# schema.net
KiCad netlist of a schematic drawn in Altium Designer
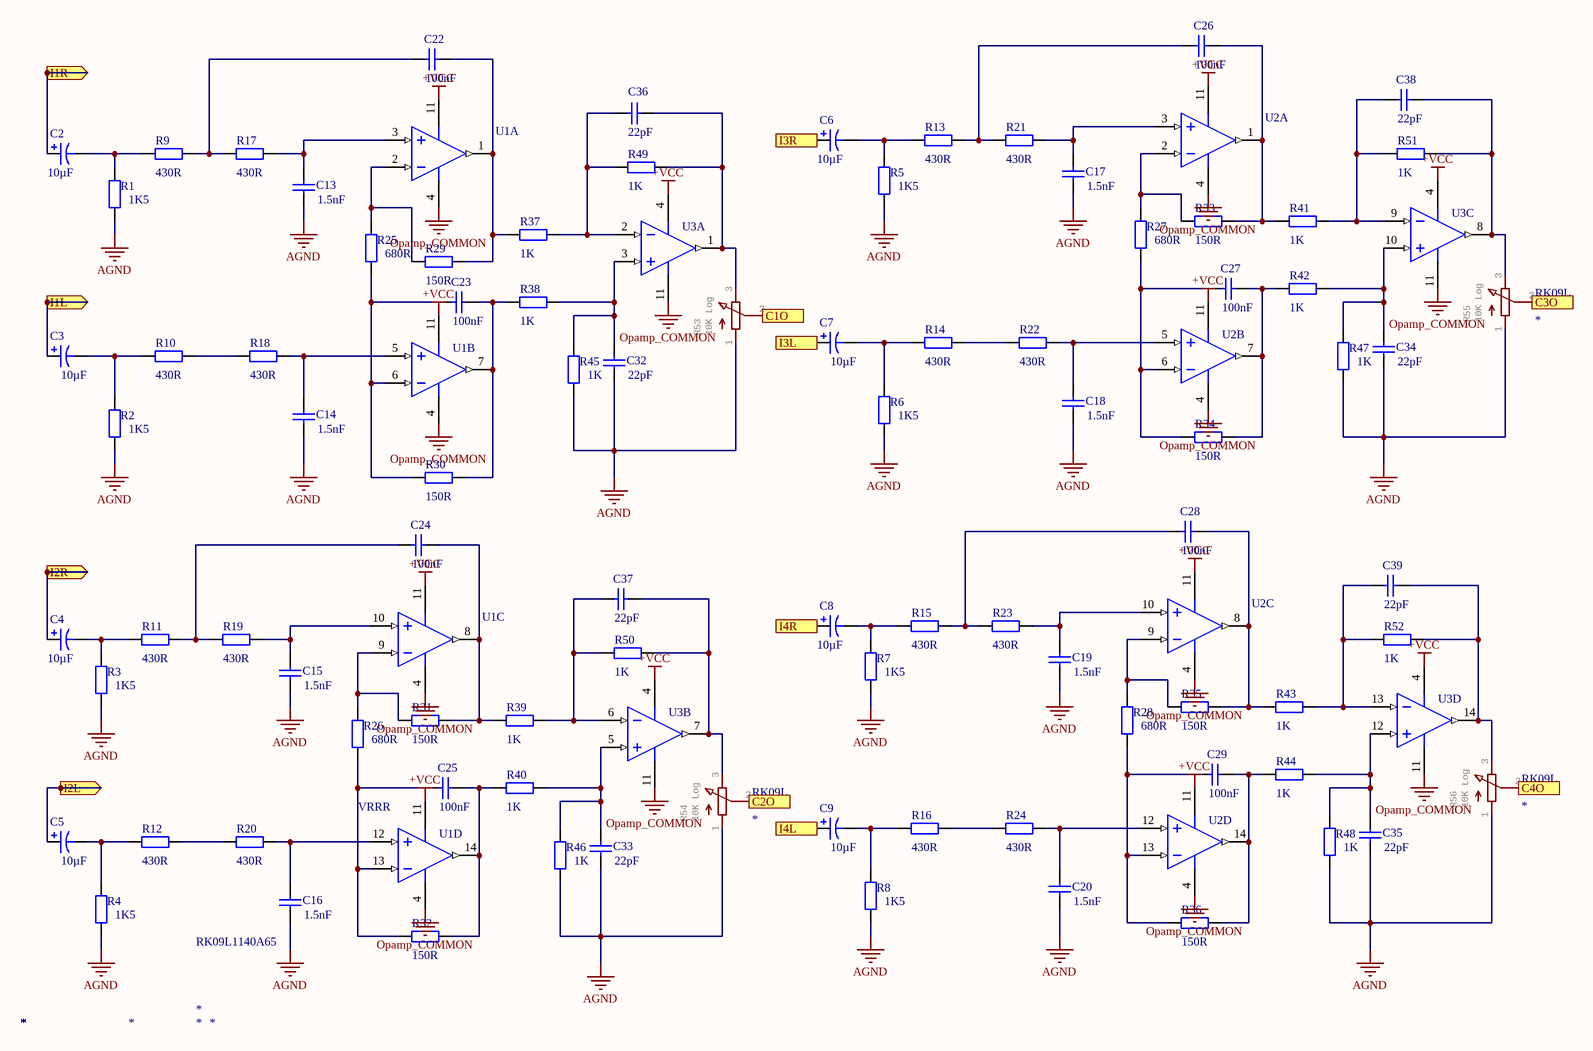
[diagram p0: schema.SchDoc]

(export (version "E")
  (design (tool "Eeschema 10.0.6"))
  (components
    (comp (ref "C2")
      (value "10µF")
      (footprint "SMD_POLAR_CAPACITOR")
      (description "Polarized Capacitor (Radial)")
      (fields (field (name "Comment") "Cap Pol1") (field (name "PUBLISHER") "Altium Limited"))
      (libsource (lib "equalizer_project") (part "Cap Pol1"))
    )
    (comp (ref "C3")
      (value "10µF")
      (footprint "SMD_POLAR_CAPACITOR")
      (description "Polarized Capacitor (Radial)")
      (fields (field (name "Comment") "Cap Pol1") (field (name "PUBLISHER") "Altium Limited"))
      (libsource (lib "Miscellaneous Devices") (part "Cap Pol1"))
    )
    (comp (ref "C4")
      (value "10µF")
      (footprint "SMD_POLAR_CAPACITOR")
      (description "Polarized Capacitor (Radial)")
      (fields (field (name "Comment") "Cap Pol1") (field (name "PUBLISHER") "Altium Limited"))
      (libsource (lib "Miscellaneous Devices") (part "Cap Pol1"))
    )
    (comp (ref "C5")
      (value "10µF")
      (footprint "SMD_POLAR_CAPACITOR")
      (description "Polarized Capacitor (Radial)")
      (fields (field (name "Comment") "Cap Pol1") (field (name "PUBLISHER") "Altium Limited"))
      (libsource (lib "Miscellaneous Devices") (part "Cap Pol1"))
    )
    (comp (ref "C6")
      (value "10µF")
      (footprint "SMD_POLAR_CAPACITOR")
      (description "Polarized Capacitor (Radial)")
      (fields (field (name "Comment") "Cap Pol1") (field (name "PUBLISHER") "Altium Limited"))
      (libsource (lib "Miscellaneous Devices") (part "Cap Pol1"))
    )
    (comp (ref "C7")
      (value "10µF")
      (footprint "SMD_POLAR_CAPACITOR")
      (description "Polarized Capacitor (Radial)")
      (fields (field (name "Comment") "Cap Pol1") (field (name "PUBLISHER") "Altium Limited"))
      (libsource (lib "Miscellaneous Devices") (part "Cap Pol1"))
    )
    (comp (ref "C8")
      (value "10µF")
      (footprint "SMD_POLAR_CAPACITOR")
      (description "Polarized Capacitor (Radial)")
      (fields (field (name "Comment") "Cap Pol1") (field (name "PUBLISHER") "Altium Limited"))
      (libsource (lib "Miscellaneous Devices") (part "Cap Pol1"))
    )
    (comp (ref "C9")
      (value "10µF")
      (footprint "SMD_POLAR_CAPACITOR")
      (description "Polarized Capacitor (Radial)")
      (fields (field (name "Comment") "Cap Pol1") (field (name "PUBLISHER") "Altium Limited"))
      (libsource (lib "Miscellaneous Devices") (part "Cap Pol1"))
    )
    (comp (ref "C13")
      (value "1.5nF")
      (footprint "SMD_CAPACITOR")
      (description "Capacitor")
      (fields (field (name "Comment") "Cap") (field (name "PUBLISHER") "Altium Limited"))
      (libsource (lib "Miscellaneous Devices") (part "Cap"))
    )
    (comp (ref "C14")
      (value "1.5nF")
      (footprint "SMD_CAPACITOR")
      (description "Capacitor")
      (fields (field (name "Comment") "Cap") (field (name "PUBLISHER") "Altium Limited"))
      (libsource (lib "Miscellaneous Devices") (part "Cap"))
    )
    (comp (ref "C15")
      (value "1.5nF")
      (footprint "SMD_CAPACITOR")
      (description "Capacitor")
      (fields (field (name "Comment") "Cap") (field (name "PUBLISHER") "Altium Limited"))
      (libsource (lib "Miscellaneous Devices") (part "Cap"))
    )
    (comp (ref "C16")
      (value "1.5nF")
      (footprint "SMD_CAPACITOR")
      (description "Capacitor")
      (fields (field (name "Comment") "Cap") (field (name "PUBLISHER") "Altium Limited"))
      (libsource (lib "Miscellaneous Devices") (part "Cap"))
    )
    (comp (ref "C17")
      (value "1.5nF")
      (footprint "SMD_CAPACITOR")
      (description "Capacitor")
      (fields (field (name "Comment") "Cap") (field (name "PUBLISHER") "Altium Limited"))
      (libsource (lib "Miscellaneous Devices") (part "Cap"))
    )
    (comp (ref "C18")
      (value "1.5nF")
      (footprint "SMD_CAPACITOR")
      (description "Capacitor")
      (fields (field (name "Comment") "Cap") (field (name "PUBLISHER") "Altium Limited"))
      (libsource (lib "Miscellaneous Devices") (part "Cap"))
    )
    (comp (ref "C19")
      (value "1.5nF")
      (footprint "SMD_CAPACITOR")
      (description "Capacitor")
      (fields (field (name "Comment") "Cap") (field (name "PUBLISHER") "Altium Limited"))
      (libsource (lib "Miscellaneous Devices") (part "Cap"))
    )
    (comp (ref "C20")
      (value "1.5nF")
      (footprint "SMD_CAPACITOR")
      (description "Capacitor")
      (fields (field (name "Comment") "Cap") (field (name "PUBLISHER") "Altium Limited"))
      (libsource (lib "Miscellaneous Devices") (part "Cap"))
    )
    (comp (ref "C22")
      (value "100nF")
      (footprint "SMD_CAPACITOR")
      (description "Capacitor")
      (fields (field (name "Comment") "Cap") (field (name "PUBLISHER") "Altium Limited"))
      (libsource (lib "Miscellaneous Devices") (part "Cap"))
    )
    (comp (ref "C23")
      (value "100nF")
      (footprint "SMD_CAPACITOR")
      (description "Capacitor")
      (fields (field (name "Comment") "Cap") (field (name "PUBLISHER") "Altium Limited"))
      (libsource (lib "Miscellaneous Devices") (part "Cap"))
    )
    (comp (ref "C24")
      (value "100nF")
      (footprint "SMD_CAPACITOR")
      (description "Capacitor")
      (fields (field (name "Comment") "Cap") (field (name "PUBLISHER") "Altium Limited"))
      (libsource (lib "Miscellaneous Devices") (part "Cap"))
    )
    (comp (ref "C25")
      (value "100nF")
      (footprint "SMD_CAPACITOR")
      (description "Capacitor")
      (fields (field (name "Comment") "Cap") (field (name "PUBLISHER") "Altium Limited"))
      (libsource (lib "Miscellaneous Devices") (part "Cap"))
    )
    (comp (ref "C26")
      (value "100nF")
      (footprint "SMD_CAPACITOR")
      (description "Capacitor")
      (fields (field (name "Comment") "Cap") (field (name "PUBLISHER") "Altium Limited"))
      (libsource (lib "Miscellaneous Devices") (part "Cap"))
    )
    (comp (ref "C27")
      (value "100nF")
      (footprint "SMD_CAPACITOR")
      (description "Capacitor")
      (fields (field (name "Comment") "Cap") (field (name "PUBLISHER") "Altium Limited"))
      (libsource (lib "Miscellaneous Devices") (part "Cap"))
    )
    (comp (ref "C28")
      (value "100nF")
      (footprint "SMD_CAPACITOR")
      (description "Capacitor")
      (fields (field (name "Comment") "Cap") (field (name "PUBLISHER") "Altium Limited"))
      (libsource (lib "Miscellaneous Devices") (part "Cap"))
    )
    (comp (ref "C29")
      (value "100nF")
      (footprint "SMD_CAPACITOR")
      (description "Capacitor")
      (fields (field (name "Comment") "Cap") (field (name "PUBLISHER") "Altium Limited"))
      (libsource (lib "Miscellaneous Devices") (part "Cap"))
    )
    (comp (ref "C32")
      (value "22pF")
      (footprint "SMD_CAPACITOR")
      (description "Capacitor")
      (fields (field (name "Comment") "Cap") (field (name "PUBLISHER") "Altium Limited"))
      (libsource (lib "Miscellaneous Devices") (part "Cap"))
    )
    (comp (ref "C33")
      (value "22pF")
      (footprint "SMD_CAPACITOR")
      (description "Capacitor")
      (fields (field (name "Comment") "Cap") (field (name "PUBLISHER") "Altium Limited"))
      (libsource (lib "Miscellaneous Devices") (part "Cap"))
    )
    (comp (ref "C34")
      (value "22pF")
      (footprint "SMD_CAPACITOR")
      (description "Capacitor")
      (fields (field (name "Comment") "Cap") (field (name "PUBLISHER") "Altium Limited"))
      (libsource (lib "Miscellaneous Devices") (part "Cap"))
    )
    (comp (ref "C35")
      (value "22pF")
      (footprint "SMD_CAPACITOR")
      (description "Capacitor")
      (fields (field (name "Comment") "Cap") (field (name "PUBLISHER") "Altium Limited"))
      (libsource (lib "Miscellaneous Devices") (part "Cap"))
    )
    (comp (ref "C36")
      (value "22pF")
      (footprint "SMD_CAPACITOR")
      (description "Capacitor")
      (fields (field (name "Comment") "Cap") (field (name "PUBLISHER") "Altium Limited"))
      (libsource (lib "Miscellaneous Devices") (part "Cap"))
    )
    (comp (ref "C37")
      (value "22pF")
      (footprint "SMD_CAPACITOR")
      (description "Capacitor")
      (fields (field (name "Comment") "Cap") (field (name "PUBLISHER") "Altium Limited"))
      (libsource (lib "Miscellaneous Devices") (part "Cap"))
    )
    (comp (ref "C38")
      (value "22pF")
      (footprint "SMD_CAPACITOR")
      (description "Capacitor")
      (fields (field (name "Comment") "Cap") (field (name "PUBLISHER") "Altium Limited"))
      (libsource (lib "Miscellaneous Devices") (part "Cap"))
    )
    (comp (ref "C39")
      (value "22pF")
      (footprint "SMD_CAPACITOR")
      (description "Capacitor")
      (fields (field (name "Comment") "Cap") (field (name "PUBLISHER") "Altium Limited"))
      (libsource (lib "Miscellaneous Devices") (part "Cap"))
    )
    (comp (ref "R1")
      (value "1K5")
      (footprint "SMD_RESISTOR")
      (description "Resistor")
      (fields (field (name "Comment") "Res2") (field (name "PUBLISHER") "Altium Limited"))
      (libsource (lib "Miscellaneous Devices") (part "Res2"))
    )
    (comp (ref "R2")
      (value "1K5")
      (footprint "SMD_RESISTOR")
      (description "Resistor")
      (fields (field (name "Comment") "Res2") (field (name "PUBLISHER") "Altium Limited"))
      (libsource (lib "Miscellaneous Devices") (part "Res2"))
    )
    (comp (ref "R3")
      (value "1K5")
      (footprint "SMD_RESISTOR")
      (description "Resistor")
      (fields (field (name "Comment") "Res2") (field (name "PUBLISHER") "Altium Limited"))
      (libsource (lib "Miscellaneous Devices") (part "Res2"))
    )
    (comp (ref "R4")
      (value "1K5")
      (footprint "SMD_RESISTOR")
      (description "Resistor")
      (fields (field (name "Comment") "Res2") (field (name "PUBLISHER") "Altium Limited"))
      (libsource (lib "Miscellaneous Devices") (part "Res2"))
    )
    (comp (ref "R5")
      (value "1K5")
      (footprint "SMD_RESISTOR")
      (description "Resistor")
      (fields (field (name "Comment") "Res2") (field (name "PUBLISHER") "Altium Limited"))
      (libsource (lib "Miscellaneous Devices") (part "Res2"))
    )
    (comp (ref "R6")
      (value "1K5")
      (footprint "SMD_RESISTOR")
      (description "Resistor")
      (fields (field (name "Comment") "Res2") (field (name "PUBLISHER") "Altium Limited"))
      (libsource (lib "Miscellaneous Devices") (part "Res2"))
    )
    (comp (ref "R7")
      (value "1K5")
      (footprint "SMD_RESISTOR")
      (description "Resistor")
      (fields (field (name "Comment") "Res2") (field (name "PUBLISHER") "Altium Limited"))
      (libsource (lib "Miscellaneous Devices") (part "Res2"))
    )
    (comp (ref "R8")
      (value "1K5")
      (footprint "SMD_RESISTOR")
      (description "Resistor")
      (fields (field (name "Comment") "Res2") (field (name "PUBLISHER") "Altium Limited"))
      (libsource (lib "Miscellaneous Devices") (part "Res2"))
    )
    (comp (ref "R9")
      (value "430R")
      (footprint "SMD_RESISTOR")
      (description "Resistor")
      (fields (field (name "Comment") "Res2") (field (name "PUBLISHER") "Altium Limited"))
      (libsource (lib "") (part "Res2_1"))
    )
    (comp (ref "R10")
      (value "430R")
      (footprint "SMD_RESISTOR")
      (description "Resistor")
      (fields (field (name "Comment") "Res2") (field (name "PUBLISHER") "Altium Limited"))
      (libsource (lib "") (part "Res2_1"))
    )
    (comp (ref "R11")
      (value "430R")
      (footprint "SMD_RESISTOR")
      (description "Resistor")
      (fields (field (name "Comment") "Res2") (field (name "PUBLISHER") "Altium Limited"))
      (libsource (lib "") (part "Res2_1"))
    )
    (comp (ref "R12")
      (value "430R")
      (footprint "SMD_RESISTOR")
      (description "Resistor")
      (fields (field (name "Comment") "Res2") (field (name "PUBLISHER") "Altium Limited"))
      (libsource (lib "") (part "Res2_1"))
    )
    (comp (ref "R13")
      (value "430R")
      (footprint "SMD_RESISTOR")
      (description "Resistor")
      (fields (field (name "Comment") "Res2") (field (name "PUBLISHER") "Altium Limited"))
      (libsource (lib "") (part "Res2_1"))
    )
    (comp (ref "R14")
      (value "430R")
      (footprint "SMD_RESISTOR")
      (description "Resistor")
      (fields (field (name "Comment") "Res2") (field (name "PUBLISHER") "Altium Limited"))
      (libsource (lib "") (part "Res2_1"))
    )
    (comp (ref "R15")
      (value "430R")
      (footprint "SMD_RESISTOR")
      (description "Resistor")
      (fields (field (name "Comment") "Res2") (field (name "PUBLISHER") "Altium Limited"))
      (libsource (lib "") (part "Res2_1"))
    )
    (comp (ref "R16")
      (value "430R")
      (footprint "SMD_RESISTOR")
      (description "Resistor")
      (fields (field (name "Comment") "Res2") (field (name "PUBLISHER") "Altium Limited"))
      (libsource (lib "") (part "Res2_1"))
    )
    (comp (ref "R17")
      (value "430R")
      (footprint "SMD_RESISTOR")
      (description "Resistor")
      (fields (field (name "Comment") "Res2") (field (name "PUBLISHER") "Altium Limited"))
      (libsource (lib "") (part "Res2_1"))
    )
    (comp (ref "R18")
      (value "430R")
      (footprint "SMD_RESISTOR")
      (description "Resistor")
      (fields (field (name "Comment") "Res2") (field (name "PUBLISHER") "Altium Limited"))
      (libsource (lib "") (part "Res2_1"))
    )
    (comp (ref "R19")
      (value "430R")
      (footprint "SMD_RESISTOR")
      (description "Resistor")
      (fields (field (name "Comment") "Res2") (field (name "PUBLISHER") "Altium Limited"))
      (libsource (lib "") (part "Res2_1"))
    )
    (comp (ref "R20")
      (value "430R")
      (footprint "SMD_RESISTOR")
      (description "Resistor")
      (fields (field (name "Comment") "Res2") (field (name "PUBLISHER") "Altium Limited"))
      (libsource (lib "") (part "Res2_1"))
    )
    (comp (ref "R21")
      (value "430R")
      (footprint "SMD_RESISTOR")
      (description "Resistor")
      (fields (field (name "Comment") "Res2") (field (name "PUBLISHER") "Altium Limited"))
      (libsource (lib "") (part "Res2_1"))
    )
    (comp (ref "R22")
      (value "430R")
      (footprint "SMD_RESISTOR")
      (description "Resistor")
      (fields (field (name "Comment") "Res2") (field (name "PUBLISHER") "Altium Limited"))
      (libsource (lib "") (part "Res2_1"))
    )
    (comp (ref "R23")
      (value "430R")
      (footprint "SMD_RESISTOR")
      (description "Resistor")
      (fields (field (name "Comment") "Res2") (field (name "PUBLISHER") "Altium Limited"))
      (libsource (lib "") (part "Res2_1"))
    )
    (comp (ref "R24")
      (value "430R")
      (footprint "SMD_RESISTOR")
      (description "Resistor")
      (fields (field (name "Comment") "Res2") (field (name "PUBLISHER") "Altium Limited"))
      (libsource (lib "") (part "Res2_1"))
    )
    (comp (ref "R25")
      (value "680R")
      (footprint "SMD_RESISTOR")
      (description "Resistor")
      (fields (field (name "Comment") "Res2") (field (name "PUBLISHER") "Altium Limited"))
      (libsource (lib "Miscellaneous Devices") (part "Res2"))
    )
    (comp (ref "R26")
      (value "680R")
      (footprint "SMD_RESISTOR")
      (description "Resistor")
      (fields (field (name "Comment") "Res2") (field (name "PUBLISHER") "Altium Limited"))
      (libsource (lib "Miscellaneous Devices") (part "Res2"))
    )
    (comp (ref "R27")
      (value "680R")
      (footprint "SMD_RESISTOR")
      (description "Resistor")
      (fields (field (name "Comment") "Res2") (field (name "PUBLISHER") "Altium Limited"))
      (libsource (lib "Miscellaneous Devices") (part "Res2"))
    )
    (comp (ref "R28")
      (value "680R")
      (footprint "SMD_RESISTOR")
      (description "Resistor")
      (fields (field (name "Comment") "Res2") (field (name "PUBLISHER") "Altium Limited"))
      (libsource (lib "Miscellaneous Devices") (part "Res2"))
    )
    (comp (ref "R29")
      (value "150R")
      (footprint "SMD_RESISTOR")
      (description "Resistor")
      (fields (field (name "Comment") "Res2") (field (name "PUBLISHER") "Altium Limited"))
      (libsource (lib "") (part "Res2_1"))
    )
    (comp (ref "R30")
      (value "150R")
      (footprint "SMD_RESISTOR")
      (description "Resistor")
      (fields (field (name "Comment") "Res2") (field (name "PUBLISHER") "Altium Limited"))
      (libsource (lib "") (part "Res2_1"))
    )
    (comp (ref "R31")
      (value "150R")
      (footprint "SMD_RESISTOR")
      (description "Resistor")
      (fields (field (name "Comment") "Res2") (field (name "PUBLISHER") "Altium Limited"))
      (libsource (lib "") (part "Res2_1"))
    )
    (comp (ref "R32")
      (value "150R")
      (footprint "SMD_RESISTOR")
      (description "Resistor")
      (fields (field (name "Comment") "Res2") (field (name "PUBLISHER") "Altium Limited"))
      (libsource (lib "") (part "Res2_1"))
    )
    (comp (ref "R33")
      (value "150R")
      (footprint "SMD_RESISTOR")
      (description "Resistor")
      (fields (field (name "Comment") "Res2") (field (name "PUBLISHER") "Altium Limited"))
      (libsource (lib "") (part "Res2_1"))
    )
    (comp (ref "R34")
      (value "150R")
      (footprint "SMD_RESISTOR")
      (description "Resistor")
      (fields (field (name "Comment") "Res2") (field (name "PUBLISHER") "Altium Limited"))
      (libsource (lib "") (part "Res2_1"))
    )
    (comp (ref "R35")
      (value "150R")
      (footprint "SMD_RESISTOR")
      (description "Resistor")
      (fields (field (name "Comment") "Res2") (field (name "PUBLISHER") "Altium Limited"))
      (libsource (lib "") (part "Res2_1"))
    )
    (comp (ref "R36")
      (value "150R")
      (footprint "SMD_RESISTOR")
      (description "Resistor")
      (fields (field (name "Comment") "Res2") (field (name "PUBLISHER") "Altium Limited"))
      (libsource (lib "") (part "Res2_1"))
    )
    (comp (ref "R37")
      (value "1K")
      (footprint "SMD_RESISTOR")
      (description "Resistor")
      (fields (field (name "Comment") "Res2") (field (name "PUBLISHER") "Altium Limited"))
      (libsource (lib "") (part "Res2_1"))
    )
    (comp (ref "R38")
      (value "1K")
      (footprint "SMD_RESISTOR")
      (description "Resistor")
      (fields (field (name "Comment") "Res2") (field (name "PUBLISHER") "Altium Limited"))
      (libsource (lib "") (part "Res2_1"))
    )
    (comp (ref "R39")
      (value "1K")
      (footprint "SMD_RESISTOR")
      (description "Resistor")
      (fields (field (name "Comment") "Res2") (field (name "PUBLISHER") "Altium Limited"))
      (libsource (lib "") (part "Res2_1"))
    )
    (comp (ref "R40")
      (value "1K")
      (footprint "SMD_RESISTOR")
      (description "Resistor")
      (fields (field (name "Comment") "Res2") (field (name "PUBLISHER") "Altium Limited"))
      (libsource (lib "") (part "Res2_1"))
    )
    (comp (ref "R41")
      (value "1K")
      (footprint "SMD_RESISTOR")
      (description "Resistor")
      (fields (field (name "Comment") "Res2") (field (name "PUBLISHER") "Altium Limited"))
      (libsource (lib "") (part "Res2_1"))
    )
    (comp (ref "R42")
      (value "1K")
      (footprint "SMD_RESISTOR")
      (description "Resistor")
      (fields (field (name "Comment") "Res2") (field (name "PUBLISHER") "Altium Limited"))
      (libsource (lib "") (part "Res2_1"))
    )
    (comp (ref "R43")
      (value "1K")
      (footprint "SMD_RESISTOR")
      (description "Resistor")
      (fields (field (name "Comment") "Res2") (field (name "PUBLISHER") "Altium Limited"))
      (libsource (lib "") (part "Res2_1"))
    )
    (comp (ref "R44")
      (value "1K")
      (footprint "SMD_RESISTOR")
      (description "Resistor")
      (fields (field (name "Comment") "Res2") (field (name "PUBLISHER") "Altium Limited"))
      (libsource (lib "") (part "Res2_1"))
    )
    (comp (ref "R45")
      (value "1K")
      (footprint "SMD_RESISTOR")
      (description "Resistor")
      (fields (field (name "Comment") "Res2") (field (name "PUBLISHER") "Altium Limited"))
      (libsource (lib "Miscellaneous Devices") (part "Res2"))
    )
    (comp (ref "R46")
      (value "1K")
      (footprint "SMD_RESISTOR")
      (description "Resistor")
      (fields (field (name "Comment") "Res2") (field (name "PUBLISHER") "Altium Limited"))
      (libsource (lib "Miscellaneous Devices") (part "Res2"))
    )
    (comp (ref "R47")
      (value "1K")
      (footprint "SMD_RESISTOR")
      (description "Resistor")
      (fields (field (name "Comment") "Res2") (field (name "PUBLISHER") "Altium Limited"))
      (libsource (lib "Miscellaneous Devices") (part "Res2"))
    )
    (comp (ref "R48")
      (value "1K")
      (footprint "SMD_RESISTOR")
      (description "Resistor")
      (fields (field (name "Comment") "Res2") (field (name "PUBLISHER") "Altium Limited"))
      (libsource (lib "Miscellaneous Devices") (part "Res2"))
    )
    (comp (ref "R49")
      (value "1K")
      (footprint "SMD_RESISTOR")
      (description "Resistor")
      (fields (field (name "Comment") "Res2") (field (name "PUBLISHER") "Altium Limited"))
      (libsource (lib "") (part "Res2_1"))
    )
    (comp (ref "R50")
      (value "1K")
      (footprint "SMD_RESISTOR")
      (description "Resistor")
      (fields (field (name "Comment") "Res2") (field (name "PUBLISHER") "Altium Limited"))
      (libsource (lib "") (part "Res2_1"))
    )
    (comp (ref "R51")
      (value "1K")
      (footprint "SMD_RESISTOR")
      (description "Resistor")
      (fields (field (name "Comment") "Res2") (field (name "PUBLISHER") "Altium Limited"))
      (libsource (lib "") (part "Res2_1"))
    )
    (comp (ref "R52")
      (value "1K")
      (footprint "SMD_RESISTOR")
      (description "Resistor")
      (fields (field (name "Comment") "Res2") (field (name "PUBLISHER") "Altium Limited"))
      (libsource (lib "") (part "Res2_1"))
    )
    (comp (ref "R53")
      (value "10K Log")
      (footprint "RK09L1140A65")
      (fields
        (field (name "ALTIUM_UNNAMED_4") "*")
        (field (name "ALTIUM_UNNAMED_5") "*")
        (field (name "ALTIUM_UNNAMED_6") "*")
        (field (name "ALTIUM_UNNAMED_7") "*")
        (field (name "ALTIUM_UNNAMED_8") "*")
        (field (name "ALTIUM_UNNAMED_9") "*")
        (field (name "ALTIUM_UNNAMED_10") "*")
        (field (name "ALTIUM_UNNAMED_11") "*")
        (field (name "ALTIUM_UNNAMED_12") "*")
        (field (name "ALTIUM_UNNAMED_13") "*")
        (field (name "LIBRARYNAME") "SD_Pots")
      )
      (libsource (lib "equalizer_project") (part "RK09L"))
    )
    (comp (ref "R54")
      (value "10K Log")
      (footprint "RK09L1140A65")
      (fields
        (field (name "ALTIUM_UNNAMED_1") "*")
        (field (name "ALTIUM_UNNAMED_2") "*")
        (field (name "ALTIUM_UNNAMED_3") "RK09L")
        (field (name "ALTIUM_UNNAMED_4") "*")
        (field (name "ALTIUM_UNNAMED_5") "*")
        (field (name "ALTIUM_UNNAMED_6") "*")
        (field (name "ALTIUM_UNNAMED_7") "*")
        (field (name "ALTIUM_UNNAMED_8") "*")
        (field (name "ALTIUM_UNNAMED_9") "*")
        (field (name "ALTIUM_UNNAMED_10") "*")
        (field (name "ALTIUM_UNNAMED_11") "*")
        (field (name "ALTIUM_UNNAMED_12") "*")
        (field (name "ALTIUM_UNNAMED_13") "*")
        (field (name "LIBRARYNAME") "SD_Pots")
      )
      (libsource (lib "equalizer_project") (part "RK09L"))
    )
    (comp (ref "R55")
      (value "10K Log")
      (footprint "RK09L1140A65")
      (fields
        (field (name "ALTIUM_UNNAMED_1") "*")
        (field (name "ALTIUM_UNNAMED_2") "*")
        (field (name "ALTIUM_UNNAMED_3") "RK09L")
        (field (name "ALTIUM_UNNAMED_4") "*")
        (field (name "ALTIUM_UNNAMED_5") "*")
        (field (name "ALTIUM_UNNAMED_6") "*")
        (field (name "ALTIUM_UNNAMED_7") "*")
        (field (name "ALTIUM_UNNAMED_8") "*")
        (field (name "ALTIUM_UNNAMED_9") "*")
        (field (name "ALTIUM_UNNAMED_10") "*")
        (field (name "ALTIUM_UNNAMED_11") "*")
        (field (name "ALTIUM_UNNAMED_12") "*")
        (field (name "ALTIUM_UNNAMED_13") "*")
        (field (name "LIBRARYNAME") "SD_Pots")
      )
      (libsource (lib "equalizer_project") (part "RK09L"))
    )
    (comp (ref "R56")
      (value "10K Log")
      (footprint "RK09L1140A65")
      (fields
        (field (name "ALTIUM_UNNAMED_1") "*")
        (field (name "ALTIUM_UNNAMED_2") "*")
        (field (name "ALTIUM_UNNAMED_3") "RK09L")
        (field (name "ALTIUM_UNNAMED_4") "*")
        (field (name "ALTIUM_UNNAMED_5") "*")
        (field (name "ALTIUM_UNNAMED_6") "*")
        (field (name "ALTIUM_UNNAMED_8") "*")
        (field (name "ALTIUM_UNNAMED_9") "*")
        (field (name "ALTIUM_UNNAMED_10") "*")
        (field (name "ALTIUM_UNNAMED_11") "*")
        (field (name "LIBRARYNAME") "SD_Pots")
      )
      (libsource (lib "equalizer_project") (part "RK09L"))
    )
    (comp (ref "U1")
      (value "OPA1664AIDR")
      (footprint "OPA1664AIDR")
      (fields (field (name "MANUFACTURER") "Texas Instruments"))
      (libsource (lib "equalizer_project") (part "CMP-0272-00211-3"))
    )
    (comp (ref "U2")
      (value "OPA1664AIDR")
      (footprint "OPA1664AIDR")
      (fields (field (name "MANUFACTURER") "Texas Instruments"))
      (libsource (lib "equalizer_project") (part "CMP-0272-00211-3"))
    )
    (comp (ref "U3")
      (value "OPA1664AIDR")
      (footprint "OPA1664AIDR")
      (fields (field (name "MANUFACTURER") "Texas Instruments"))
      (libsource (lib "equalizer_project") (part "CMP-0272-00211-3"))
    )
    (comp (ref "VRRR")
      (value "RK09L1140A65")
      (footprint "PcbLib1:RK09L1140A65")
      (description "Variable Resistor")
      (fields (field (name "MOUSER2 PART NUMBER") "688-RK09L1140A65"))
      (libsource (lib "*") (part "RK09L1140A65"))
    )
  )
  (nets
    (net (code "1") (name "+VCC") (class "Default")
      (node (ref "U1") (pin "11") (pinfunction "V-_11") (pintype "power_in"))
      (node (ref "U2") (pin "11") (pinfunction "V-_11") (pintype "power_in"))
      (node (ref "U3") (pin "4") (pinfunction "V+_4") (pintype "power_in"))
    )
    (net (code "2") (name "/C1O") (class "Default")
      (node (ref "R53") (pin "2") (pinfunction "2_2") (pintype "passive"))
    )
    (net (code "3") (name "/C2O") (class "Default")
      (node (ref "R54") (pin "2") (pinfunction "2_2") (pintype "passive"))
    )
    (net (code "4") (name "/C3O") (class "Default")
      (node (ref "R55") (pin "2") (pinfunction "2_2") (pintype "passive"))
    )
    (net (code "5") (name "/C4O") (class "Default")
      (node (ref "R56") (pin "2") (pinfunction "2_2") (pintype "passive"))
    )
    (net (code "6") (name "/I1L") (class "Default")
      (node (ref "C3") (pin "1") (pinfunction "1_1") (pintype "passive"))
    )
    (net (code "7") (name "/I1R") (class "Default")
      (node (ref "C2") (pin "1") (pinfunction "1_1") (pintype "passive"))
    )
    (net (code "8") (name "/I2L") (class "Default")
      (node (ref "C5") (pin "1") (pinfunction "1_1") (pintype "passive"))
    )
    (net (code "9") (name "/I2R") (class "Default")
      (node (ref "C4") (pin "1") (pinfunction "1_1") (pintype "passive"))
    )
    (net (code "10") (name "/I3L") (class "Default")
      (node (ref "C7") (pin "1") (pinfunction "1_1") (pintype "passive"))
    )
    (net (code "11") (name "/I3R") (class "Default")
      (node (ref "C6") (pin "1") (pinfunction "1_1") (pintype "passive"))
    )
    (net (code "12") (name "/I4L") (class "Default")
      (node (ref "C9") (pin "1") (pinfunction "1_1") (pintype "passive"))
    )
    (net (code "13") (name "/I4R") (class "Default")
      (node (ref "C8") (pin "1") (pinfunction "1_1") (pintype "passive"))
    )
    (net (code "14") (name "AGND") (class "Default")
      (node (ref "C13") (pin "1") (pinfunction "1_1") (pintype "passive"))
      (node (ref "C14") (pin "1") (pinfunction "1_1") (pintype "passive"))
      (node (ref "C15") (pin "1") (pinfunction "1_1") (pintype "passive"))
      (node (ref "C16") (pin "1") (pinfunction "1_1") (pintype "passive"))
      (node (ref "C17") (pin "1") (pinfunction "1_1") (pintype "passive"))
      (node (ref "C18") (pin "1") (pinfunction "1_1") (pintype "passive"))
      (node (ref "C19") (pin "1") (pinfunction "1_1") (pintype "passive"))
      (node (ref "C20") (pin "1") (pinfunction "1_1") (pintype "passive"))
      (node (ref "C32") (pin "1") (pinfunction "1_1") (pintype "passive"))
      (node (ref "C33") (pin "1") (pinfunction "1_1") (pintype "passive"))
      (node (ref "C34") (pin "1") (pinfunction "1_1") (pintype "passive"))
      (node (ref "C35") (pin "1") (pinfunction "1_1") (pintype "passive"))
      (node (ref "R1") (pin "1") (pinfunction "1_1") (pintype "passive"))
      (node (ref "R2") (pin "1") (pinfunction "1_1") (pintype "passive"))
      (node (ref "R3") (pin "1") (pinfunction "1_1") (pintype "passive"))
      (node (ref "R4") (pin "1") (pinfunction "1_1") (pintype "passive"))
      (node (ref "R45") (pin "1") (pinfunction "1_1") (pintype "passive"))
      (node (ref "R46") (pin "1") (pinfunction "1_1") (pintype "passive"))
      (node (ref "R47") (pin "1") (pinfunction "1_1") (pintype "passive"))
      (node (ref "R48") (pin "1") (pinfunction "1_1") (pintype "passive"))
      (node (ref "R5") (pin "1") (pinfunction "1_1") (pintype "passive"))
      (node (ref "R53") (pin "1") (pinfunction "1_1") (pintype "passive"))
      (node (ref "R54") (pin "1") (pinfunction "1_1") (pintype "passive"))
      (node (ref "R55") (pin "1") (pinfunction "1_1") (pintype "passive"))
      (node (ref "R56") (pin "1") (pinfunction "1_1") (pintype "passive"))
      (node (ref "R6") (pin "1") (pinfunction "1_1") (pintype "passive"))
      (node (ref "R7") (pin "1") (pinfunction "1_1") (pintype "passive"))
      (node (ref "R8") (pin "1") (pinfunction "1_1") (pintype "passive"))
    )
    (net (code "15") (name "Net-(C2-Pad2)") (class "Default")
      (node (ref "C2") (pin "2") (pinfunction "2_2") (pintype "passive"))
      (node (ref "R1") (pin "2") (pinfunction "2_2") (pintype "passive"))
      (node (ref "R9") (pin "1") (pinfunction "1_1") (pintype "passive"))
    )
    (net (code "16") (name "Net-(C3-Pad2)") (class "Default")
      (node (ref "C3") (pin "2") (pinfunction "2_2") (pintype "passive"))
      (node (ref "R10") (pin "1") (pinfunction "1_1") (pintype "passive"))
      (node (ref "R2") (pin "2") (pinfunction "2_2") (pintype "passive"))
    )
    (net (code "17") (name "Net-(C4-Pad2)") (class "Default")
      (node (ref "C4") (pin "2") (pinfunction "2_2") (pintype "passive"))
      (node (ref "R11") (pin "1") (pinfunction "1_1") (pintype "passive"))
      (node (ref "R3") (pin "2") (pinfunction "2_2") (pintype "passive"))
    )
    (net (code "18") (name "Net-(C5-Pad2)") (class "Default")
      (node (ref "C5") (pin "2") (pinfunction "2_2") (pintype "passive"))
      (node (ref "R12") (pin "1") (pinfunction "1_1") (pintype "passive"))
      (node (ref "R4") (pin "2") (pinfunction "2_2") (pintype "passive"))
    )
    (net (code "19") (name "Net-(C6-Pad2)") (class "Default")
      (node (ref "C6") (pin "2") (pinfunction "2_2") (pintype "passive"))
      (node (ref "R13") (pin "1") (pinfunction "1_1") (pintype "passive"))
      (node (ref "R5") (pin "2") (pinfunction "2_2") (pintype "passive"))
    )
    (net (code "20") (name "Net-(C7-Pad2)") (class "Default")
      (node (ref "C7") (pin "2") (pinfunction "2_2") (pintype "passive"))
      (node (ref "R14") (pin "1") (pinfunction "1_1") (pintype "passive"))
      (node (ref "R6") (pin "2") (pinfunction "2_2") (pintype "passive"))
    )
    (net (code "21") (name "Net-(C8-Pad2)") (class "Default")
      (node (ref "C8") (pin "2") (pinfunction "2_2") (pintype "passive"))
      (node (ref "R15") (pin "1") (pinfunction "1_1") (pintype "passive"))
      (node (ref "R7") (pin "2") (pinfunction "2_2") (pintype "passive"))
    )
    (net (code "22") (name "Net-(C9-Pad2)") (class "Default")
      (node (ref "C9") (pin "2") (pinfunction "2_2") (pintype "passive"))
      (node (ref "R16") (pin "1") (pinfunction "1_1") (pintype "passive"))
      (node (ref "R8") (pin "2") (pinfunction "2_2") (pintype "passive"))
    )
    (net (code "23") (name "Net-(C22-Pad1)") (class "Default")
      (node (ref "C22") (pin "1") (pinfunction "1_1") (pintype "passive"))
      (node (ref "R17") (pin "1") (pinfunction "1_1") (pintype "passive"))
      (node (ref "R9") (pin "2") (pinfunction "2_2") (pintype "passive"))
    )
    (net (code "24") (name "Net-(C24-Pad1)") (class "Default")
      (node (ref "C24") (pin "1") (pinfunction "1_1") (pintype "passive"))
      (node (ref "R11") (pin "2") (pinfunction "2_2") (pintype "passive"))
      (node (ref "R19") (pin "1") (pinfunction "1_1") (pintype "passive"))
    )
    (net (code "25") (name "Net-(C26-Pad1)") (class "Default")
      (node (ref "C26") (pin "1") (pinfunction "1_1") (pintype "passive"))
      (node (ref "R13") (pin "2") (pinfunction "2_2") (pintype "passive"))
      (node (ref "R21") (pin "1") (pinfunction "1_1") (pintype "passive"))
    )
    (net (code "26") (name "Net-(C28-Pad1)") (class "Default")
      (node (ref "C28") (pin "1") (pinfunction "1_1") (pintype "passive"))
      (node (ref "R15") (pin "2") (pinfunction "2_2") (pintype "passive"))
      (node (ref "R23") (pin "1") (pinfunction "1_1") (pintype "passive"))
    )
    (net (code "27") (name "Net-(R10-Pad2)") (class "Default")
      (node (ref "R10") (pin "2") (pinfunction "2_2") (pintype "passive"))
      (node (ref "R18") (pin "1") (pinfunction "1_1") (pintype "passive"))
    )
    (net (code "28") (name "Net-(R12-Pad2)") (class "Default")
      (node (ref "R12") (pin "2") (pinfunction "2_2") (pintype "passive"))
      (node (ref "R20") (pin "1") (pinfunction "1_1") (pintype "passive"))
    )
    (net (code "29") (name "Net-(R14-Pad2)") (class "Default")
      (node (ref "R14") (pin "2") (pinfunction "2_2") (pintype "passive"))
      (node (ref "R22") (pin "1") (pinfunction "1_1") (pintype "passive"))
    )
    (net (code "30") (name "Net-(R16-Pad2)") (class "Default")
      (node (ref "R16") (pin "2") (pinfunction "2_2") (pintype "passive"))
      (node (ref "R24") (pin "1") (pinfunction "1_1") (pintype "passive"))
    )
    (net (code "31") (name "Net-(U1A-IN_A+)") (class "Default")
      (node (ref "C13") (pin "2") (pinfunction "2_2") (pintype "passive"))
      (node (ref "R17") (pin "2") (pinfunction "2_2") (pintype "passive"))
      (node (ref "U1") (pin "3") (pinfunction "IN_A+_3") (pintype "input"))
    )
    (net (code "32") (name "Net-(U1A-IN_A-)") (class "Default")
      (node (ref "R25") (pin "2") (pinfunction "2_2") (pintype "passive"))
      (node (ref "R29") (pin "1") (pinfunction "1_1") (pintype "passive"))
      (node (ref "U1") (pin "2") (pinfunction "IN_A-_2") (pintype "input"))
    )
    (net (code "33") (name "Net-(U1A-OUT_A)") (class "Default")
      (node (ref "C22") (pin "2") (pinfunction "2_2") (pintype "passive"))
      (node (ref "R29") (pin "2") (pinfunction "2_2") (pintype "passive"))
      (node (ref "R37") (pin "1") (pinfunction "1_1") (pintype "passive"))
      (node (ref "U1") (pin "1") (pinfunction "OUT_A_1") (pintype "output"))
    )
    (net (code "34") (name "Net-(U1B-IN_B+)") (class "Default")
      (node (ref "C14") (pin "2") (pinfunction "2_2") (pintype "passive"))
      (node (ref "R18") (pin "2") (pinfunction "2_2") (pintype "passive"))
      (node (ref "U1") (pin "5") (pinfunction "IN_B+_5") (pintype "input"))
    )
    (net (code "35") (name "Net-(U1B-IN_B-)") (class "Default")
      (node (ref "C23") (pin "1") (pinfunction "1_1") (pintype "passive"))
      (node (ref "R25") (pin "1") (pinfunction "1_1") (pintype "passive"))
      (node (ref "R30") (pin "1") (pinfunction "1_1") (pintype "passive"))
      (node (ref "U1") (pin "6") (pinfunction "IN_B-_6") (pintype "input"))
    )
    (net (code "36") (name "Net-(U1B-OUT_B)") (class "Default")
      (node (ref "C23") (pin "2") (pinfunction "2_2") (pintype "passive"))
      (node (ref "R30") (pin "2") (pinfunction "2_2") (pintype "passive"))
      (node (ref "R38") (pin "1") (pinfunction "1_1") (pintype "passive"))
      (node (ref "U1") (pin "7") (pinfunction "OUT_B_7") (pintype "output"))
    )
    (net (code "37") (name "Net-(U1C-IN_C+)") (class "Default")
      (node (ref "C15") (pin "2") (pinfunction "2_2") (pintype "passive"))
      (node (ref "R19") (pin "2") (pinfunction "2_2") (pintype "passive"))
      (node (ref "U1") (pin "10") (pinfunction "IN_C+_10") (pintype "input"))
    )
    (net (code "38") (name "Net-(U1C-IN_C-)") (class "Default")
      (node (ref "R26") (pin "2") (pinfunction "2_2") (pintype "passive"))
      (node (ref "R31") (pin "1") (pinfunction "1_1") (pintype "passive"))
      (node (ref "U1") (pin "9") (pinfunction "IN_C-_9") (pintype "input"))
    )
    (net (code "39") (name "Net-(U1C-OUT_C)") (class "Default")
      (node (ref "C24") (pin "2") (pinfunction "2_2") (pintype "passive"))
      (node (ref "R31") (pin "2") (pinfunction "2_2") (pintype "passive"))
      (node (ref "R39") (pin "1") (pinfunction "1_1") (pintype "passive"))
      (node (ref "U1") (pin "8") (pinfunction "OUT_C_8") (pintype "output"))
    )
    (net (code "40") (name "Net-(U1D-IN_D+)") (class "Default")
      (node (ref "C16") (pin "2") (pinfunction "2_2") (pintype "passive"))
      (node (ref "R20") (pin "2") (pinfunction "2_2") (pintype "passive"))
      (node (ref "U1") (pin "12") (pinfunction "IN_D+_12") (pintype "input"))
    )
    (net (code "41") (name "Net-(U1D-IN_D-)") (class "Default")
      (node (ref "C25") (pin "1") (pinfunction "1_1") (pintype "passive"))
      (node (ref "R26") (pin "1") (pinfunction "1_1") (pintype "passive"))
      (node (ref "R32") (pin "1") (pinfunction "1_1") (pintype "passive"))
      (node (ref "U1") (pin "13") (pinfunction "IN_D-_13") (pintype "input"))
    )
    (net (code "42") (name "Net-(U1D-OUT_D)") (class "Default")
      (node (ref "C25") (pin "2") (pinfunction "2_2") (pintype "passive"))
      (node (ref "R32") (pin "2") (pinfunction "2_2") (pintype "passive"))
      (node (ref "R40") (pin "1") (pinfunction "1_1") (pintype "passive"))
      (node (ref "U1") (pin "14") (pinfunction "OUT_D_14") (pintype "output"))
    )
    (net (code "43") (name "Net-(U2A-IN_A+)") (class "Default")
      (node (ref "C17") (pin "2") (pinfunction "2_2") (pintype "passive"))
      (node (ref "R21") (pin "2") (pinfunction "2_2") (pintype "passive"))
      (node (ref "U2") (pin "3") (pinfunction "IN_A+_3") (pintype "input"))
    )
    (net (code "44") (name "Net-(U2A-IN_A-)") (class "Default")
      (node (ref "R27") (pin "2") (pinfunction "2_2") (pintype "passive"))
      (node (ref "R33") (pin "1") (pinfunction "1_1") (pintype "passive"))
      (node (ref "U2") (pin "2") (pinfunction "IN_A-_2") (pintype "input"))
    )
    (net (code "45") (name "Net-(U2A-OUT_A)") (class "Default")
      (node (ref "C26") (pin "2") (pinfunction "2_2") (pintype "passive"))
      (node (ref "R33") (pin "2") (pinfunction "2_2") (pintype "passive"))
      (node (ref "R41") (pin "1") (pinfunction "1_1") (pintype "passive"))
      (node (ref "U2") (pin "1") (pinfunction "OUT_A_1") (pintype "output"))
    )
    (net (code "46") (name "Net-(U2B-IN_B+)") (class "Default")
      (node (ref "C18") (pin "2") (pinfunction "2_2") (pintype "passive"))
      (node (ref "R22") (pin "2") (pinfunction "2_2") (pintype "passive"))
      (node (ref "U2") (pin "5") (pinfunction "IN_B+_5") (pintype "input"))
    )
    (net (code "47") (name "Net-(U2B-IN_B-)") (class "Default")
      (node (ref "C27") (pin "1") (pinfunction "1_1") (pintype "passive"))
      (node (ref "R27") (pin "1") (pinfunction "1_1") (pintype "passive"))
      (node (ref "R34") (pin "1") (pinfunction "1_1") (pintype "passive"))
      (node (ref "U2") (pin "6") (pinfunction "IN_B-_6") (pintype "input"))
    )
    (net (code "48") (name "Net-(U2B-OUT_B)") (class "Default")
      (node (ref "C27") (pin "2") (pinfunction "2_2") (pintype "passive"))
      (node (ref "R34") (pin "2") (pinfunction "2_2") (pintype "passive"))
      (node (ref "R42") (pin "1") (pinfunction "1_1") (pintype "passive"))
      (node (ref "U2") (pin "7") (pinfunction "OUT_B_7") (pintype "output"))
    )
    (net (code "49") (name "Net-(U2C-IN_C+)") (class "Default")
      (node (ref "C19") (pin "2") (pinfunction "2_2") (pintype "passive"))
      (node (ref "R23") (pin "2") (pinfunction "2_2") (pintype "passive"))
      (node (ref "U2") (pin "10") (pinfunction "IN_C+_10") (pintype "input"))
    )
    (net (code "50") (name "Net-(U2C-IN_C-)") (class "Default")
      (node (ref "R28") (pin "2") (pinfunction "2_2") (pintype "passive"))
      (node (ref "R35") (pin "1") (pinfunction "1_1") (pintype "passive"))
      (node (ref "U2") (pin "9") (pinfunction "IN_C-_9") (pintype "input"))
    )
    (net (code "51") (name "Net-(U2C-OUT_C)") (class "Default")
      (node (ref "C28") (pin "2") (pinfunction "2_2") (pintype "passive"))
      (node (ref "R35") (pin "2") (pinfunction "2_2") (pintype "passive"))
      (node (ref "R43") (pin "1") (pinfunction "1_1") (pintype "passive"))
      (node (ref "U2") (pin "8") (pinfunction "OUT_C_8") (pintype "output"))
    )
    (net (code "52") (name "Net-(U2D-IN_D+)") (class "Default")
      (node (ref "C20") (pin "2") (pinfunction "2_2") (pintype "passive"))
      (node (ref "R24") (pin "2") (pinfunction "2_2") (pintype "passive"))
      (node (ref "U2") (pin "12") (pinfunction "IN_D+_12") (pintype "input"))
    )
    (net (code "53") (name "Net-(U2D-IN_D-)") (class "Default")
      (node (ref "C29") (pin "1") (pinfunction "1_1") (pintype "passive"))
      (node (ref "R28") (pin "1") (pinfunction "1_1") (pintype "passive"))
      (node (ref "R36") (pin "1") (pinfunction "1_1") (pintype "passive"))
      (node (ref "U2") (pin "13") (pinfunction "IN_D-_13") (pintype "input"))
    )
    (net (code "54") (name "Net-(U2D-OUT_D)") (class "Default")
      (node (ref "C29") (pin "2") (pinfunction "2_2") (pintype "passive"))
      (node (ref "R36") (pin "2") (pinfunction "2_2") (pintype "passive"))
      (node (ref "R44") (pin "1") (pinfunction "1_1") (pintype "passive"))
      (node (ref "U2") (pin "14") (pinfunction "OUT_D_14") (pintype "output"))
    )
    (net (code "55") (name "Net-(U3A-IN_A+)") (class "Default")
      (node (ref "C32") (pin "2") (pinfunction "2_2") (pintype "passive"))
      (node (ref "R38") (pin "2") (pinfunction "2_2") (pintype "passive"))
      (node (ref "R45") (pin "2") (pinfunction "2_2") (pintype "passive"))
      (node (ref "U3") (pin "3") (pinfunction "IN_A+_3") (pintype "input"))
    )
    (net (code "56") (name "Net-(U3A-IN_A-)") (class "Default")
      (node (ref "C36") (pin "1") (pinfunction "1_1") (pintype "passive"))
      (node (ref "R37") (pin "2") (pinfunction "2_2") (pintype "passive"))
      (node (ref "R49") (pin "1") (pinfunction "1_1") (pintype "passive"))
      (node (ref "U3") (pin "2") (pinfunction "IN_A-_2") (pintype "input"))
    )
    (net (code "57") (name "Net-(U3A-OUT_A)") (class "Default")
      (node (ref "C36") (pin "2") (pinfunction "2_2") (pintype "passive"))
      (node (ref "R49") (pin "2") (pinfunction "2_2") (pintype "passive"))
      (node (ref "R53") (pin "3") (pinfunction "3_3") (pintype "passive"))
      (node (ref "U3") (pin "1") (pinfunction "OUT_A_1") (pintype "output"))
    )
    (net (code "58") (name "Net-(U3B-IN_B+)") (class "Default")
      (node (ref "C33") (pin "2") (pinfunction "2_2") (pintype "passive"))
      (node (ref "R40") (pin "2") (pinfunction "2_2") (pintype "passive"))
      (node (ref "R46") (pin "2") (pinfunction "2_2") (pintype "passive"))
      (node (ref "U3") (pin "5") (pinfunction "IN_B+_5") (pintype "input"))
    )
    (net (code "59") (name "Net-(U3B-IN_B-)") (class "Default")
      (node (ref "C37") (pin "1") (pinfunction "1_1") (pintype "passive"))
      (node (ref "R39") (pin "2") (pinfunction "2_2") (pintype "passive"))
      (node (ref "R50") (pin "1") (pinfunction "1_1") (pintype "passive"))
      (node (ref "U3") (pin "6") (pinfunction "IN_B-_6") (pintype "input"))
    )
    (net (code "60") (name "Net-(U3B-OUT_B)") (class "Default")
      (node (ref "C37") (pin "2") (pinfunction "2_2") (pintype "passive"))
      (node (ref "R50") (pin "2") (pinfunction "2_2") (pintype "passive"))
      (node (ref "R54") (pin "3") (pinfunction "3_3") (pintype "passive"))
      (node (ref "U3") (pin "7") (pinfunction "OUT_B_7") (pintype "output"))
    )
    (net (code "61") (name "Net-(U3C-IN_C+)") (class "Default")
      (node (ref "C34") (pin "2") (pinfunction "2_2") (pintype "passive"))
      (node (ref "R42") (pin "2") (pinfunction "2_2") (pintype "passive"))
      (node (ref "R47") (pin "2") (pinfunction "2_2") (pintype "passive"))
      (node (ref "U3") (pin "10") (pinfunction "IN_C+_10") (pintype "input"))
    )
    (net (code "62") (name "Net-(U3C-IN_C-)") (class "Default")
      (node (ref "C38") (pin "1") (pinfunction "1_1") (pintype "passive"))
      (node (ref "R41") (pin "2") (pinfunction "2_2") (pintype "passive"))
      (node (ref "R51") (pin "1") (pinfunction "1_1") (pintype "passive"))
      (node (ref "U3") (pin "9") (pinfunction "IN_C-_9") (pintype "input"))
    )
    (net (code "63") (name "Net-(U3C-OUT_C)") (class "Default")
      (node (ref "C38") (pin "2") (pinfunction "2_2") (pintype "passive"))
      (node (ref "R51") (pin "2") (pinfunction "2_2") (pintype "passive"))
      (node (ref "R55") (pin "3") (pinfunction "3_3") (pintype "passive"))
      (node (ref "U3") (pin "8") (pinfunction "OUT_C_8") (pintype "output"))
    )
    (net (code "64") (name "Net-(U3D-IN_D+)") (class "Default")
      (node (ref "C35") (pin "2") (pinfunction "2_2") (pintype "passive"))
      (node (ref "R44") (pin "2") (pinfunction "2_2") (pintype "passive"))
      (node (ref "R48") (pin "2") (pinfunction "2_2") (pintype "passive"))
      (node (ref "U3") (pin "12") (pinfunction "IN_D+_12") (pintype "input"))
    )
    (net (code "65") (name "Net-(U3D-IN_D-)") (class "Default")
      (node (ref "C39") (pin "1") (pinfunction "1_1") (pintype "passive"))
      (node (ref "R43") (pin "2") (pinfunction "2_2") (pintype "passive"))
      (node (ref "R52") (pin "1") (pinfunction "1_1") (pintype "passive"))
      (node (ref "U3") (pin "13") (pinfunction "IN_D-_13") (pintype "input"))
    )
    (net (code "66") (name "Net-(U3D-OUT_D)") (class "Default")
      (node (ref "C39") (pin "2") (pinfunction "2_2") (pintype "passive"))
      (node (ref "R52") (pin "2") (pinfunction "2_2") (pintype "passive"))
      (node (ref "R56") (pin "3") (pinfunction "3_3") (pintype "passive"))
      (node (ref "U3") (pin "14") (pinfunction "OUT_D_14") (pintype "output"))
    )
    (net (code "67") (name "Opamp_COMMON") (class "Default")
      (node (ref "U1") (pin "4") (pinfunction "V+_4") (pintype "power_in"))
      (node (ref "U2") (pin "4") (pinfunction "V+_4") (pintype "power_in"))
      (node (ref "U3") (pin "11") (pinfunction "V-_11") (pintype "power_in"))
    )
  )
)
